# BC95_SIM.net
KiCad netlist of a schematic drawn in Altium Designer
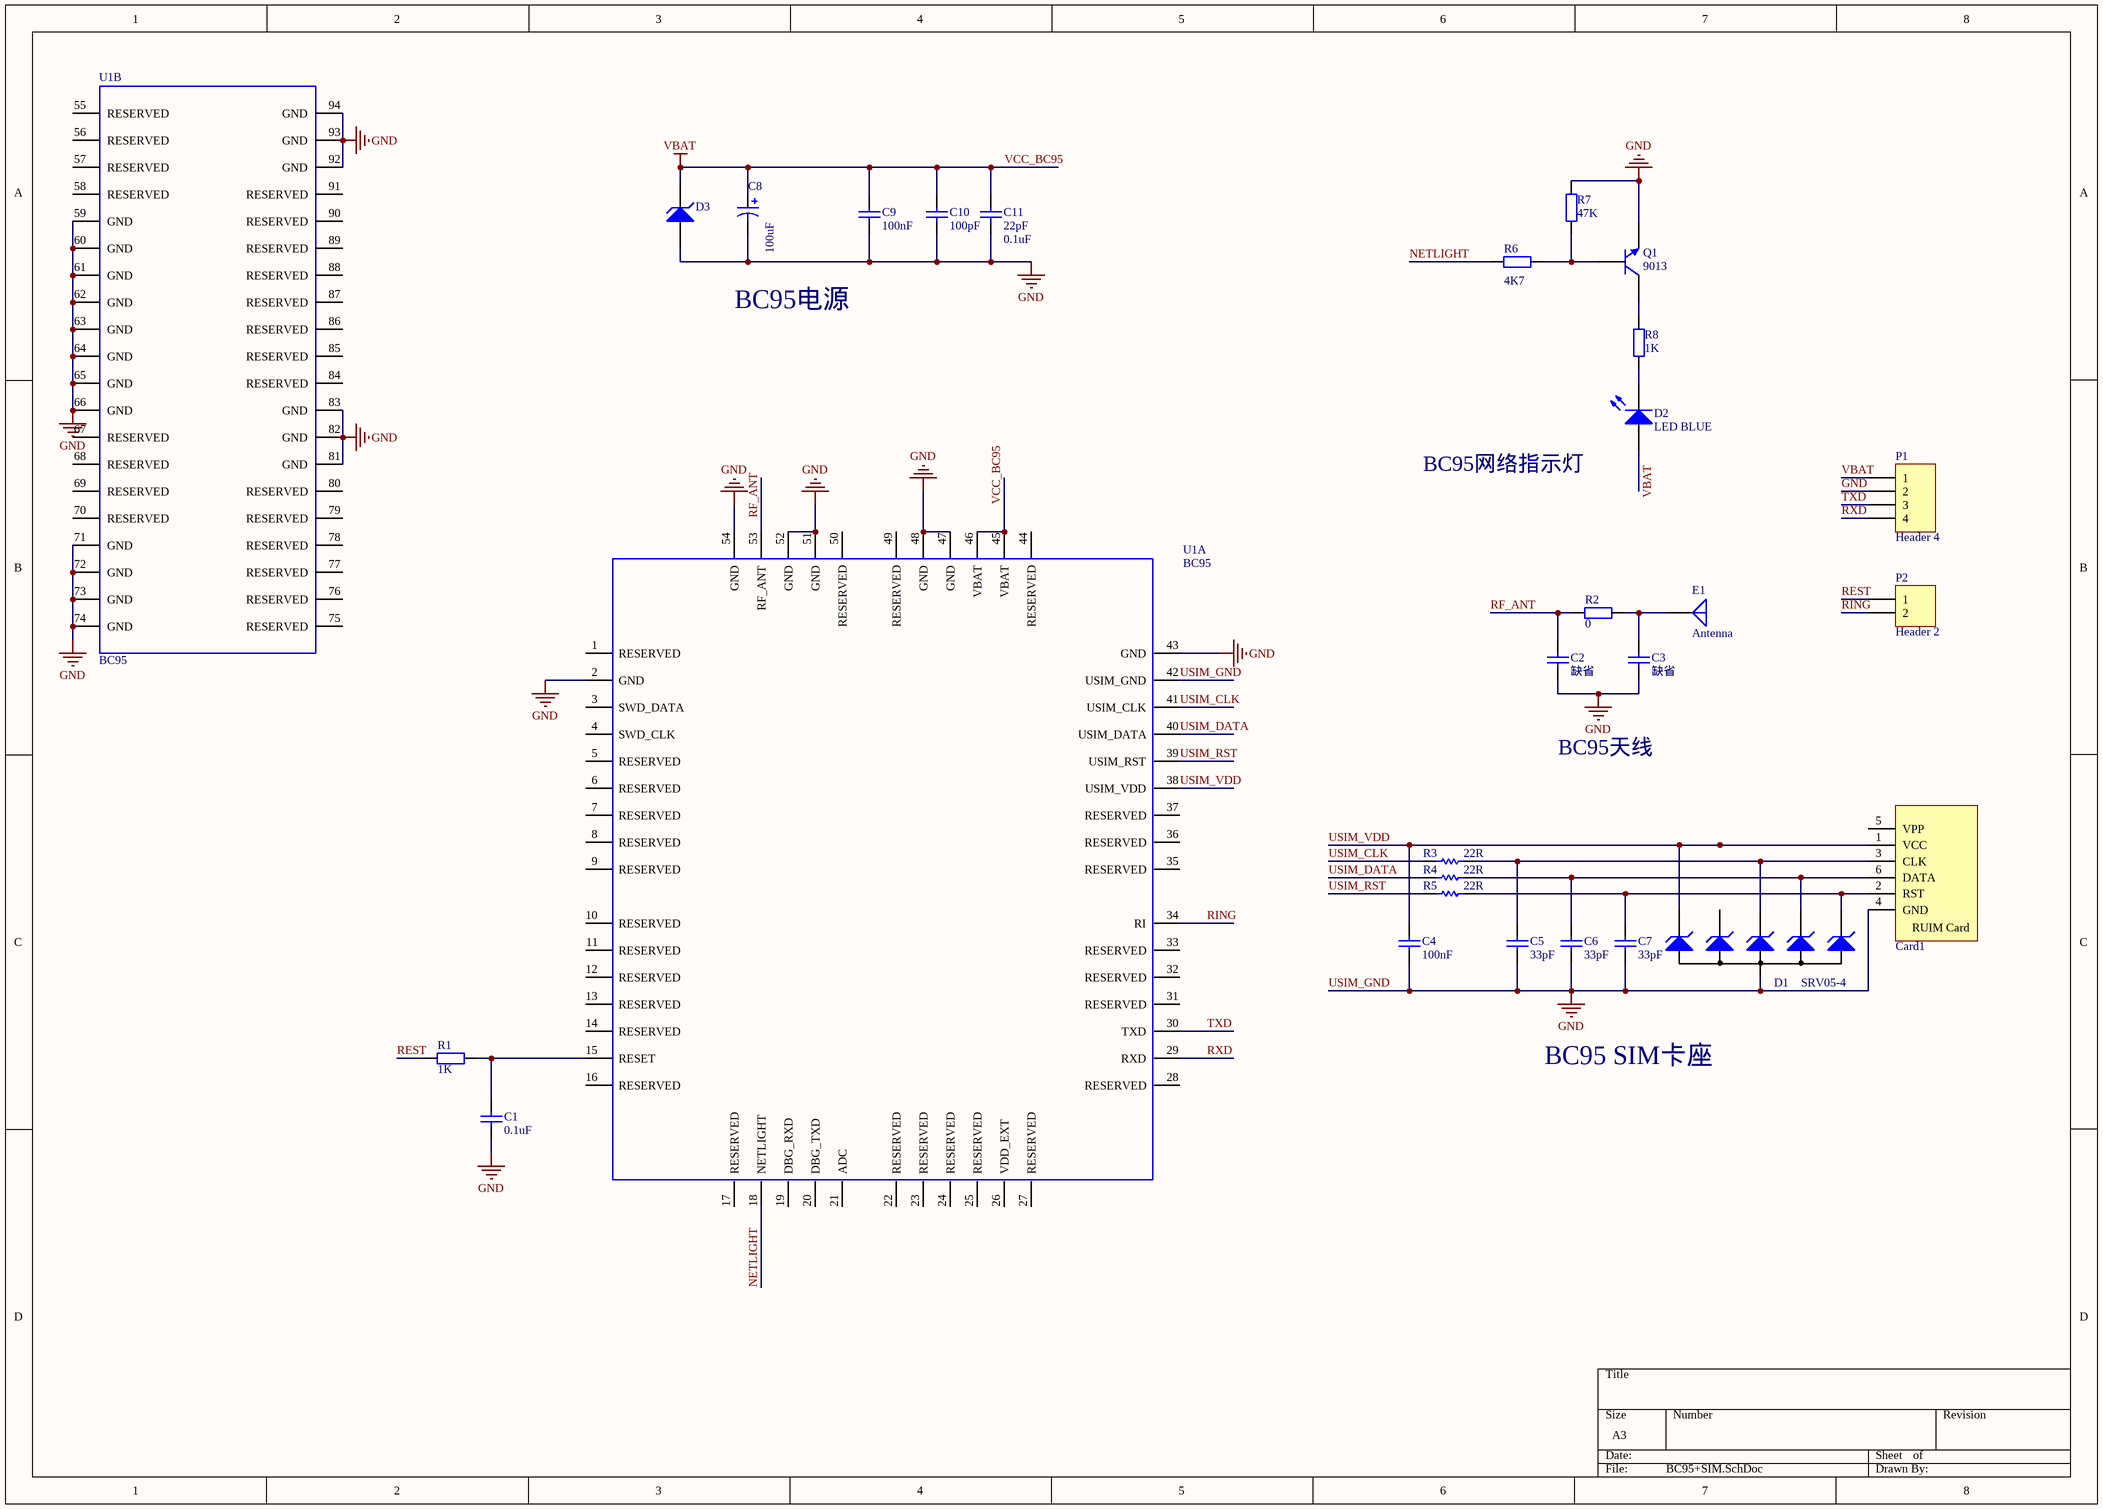
[diagram p0: BC95+SIM.SchDoc]

(export (version "E")
  (design (tool "Eeschema 10.0.6"))
  (components
    (comp (ref "C1")
      (value "0.1uF")
      (footprint "0603")
      (description "Capacitor")
      (fields (field (name "PUBLISHER") "Altium Limited"))
      (libsource (lib "Miscellaneous Devices") (part "Cap"))
    )
    (comp (ref "C2")
      (value "缺省")
      (footprint "0603")
      (description "Capacitor")
      (fields (field (name "PUBLISHER") "Altium Limited"))
      (libsource (lib "Miscellaneous Devices") (part "Cap"))
    )
    (comp (ref "C3")
      (value "缺省")
      (footprint "0603")
      (description "Capacitor")
      (fields (field (name "PUBLISHER") "Altium Limited"))
      (libsource (lib "Miscellaneous Devices") (part "Cap"))
    )
    (comp (ref "C4")
      (value "100nF")
      (footprint "0603")
      (description "Capacitor")
      (fields (field (name "PUBLISHER") "Altium Limited"))
      (libsource (lib "Miscellaneous Devices") (part "Cap"))
    )
    (comp (ref "C5")
      (value "33pF")
      (footprint "0603")
      (description "Capacitor")
      (fields (field (name "PUBLISHER") "Altium Limited"))
      (libsource (lib "Miscellaneous Devices") (part "Cap"))
    )
    (comp (ref "C6")
      (value "33pF")
      (footprint "0603")
      (description "Capacitor")
      (fields (field (name "PUBLISHER") "Altium Limited"))
      (libsource (lib "Miscellaneous Devices") (part "Cap"))
    )
    (comp (ref "C7")
      (value "33pF")
      (footprint "0603")
      (description "Capacitor")
      (fields (field (name "PUBLISHER") "Altium Limited"))
      (libsource (lib "Miscellaneous Devices") (part "Cap"))
    )
    (comp (ref "C8")
      (value "100uF")
      (footprint "1206")
      (description "插件 电解电容 13*21")
      (fields (field (name "PUBLISHER") "Altium Limited"))
      (libsource (lib "Miscellaneous Devices") (part "Cap Pol1"))
    )
    (comp (ref "C9")
      (value "100nF")
      (footprint "0603")
      (description "Capacitor")
      (fields (field (name "PUBLISHER") "Altium Limited"))
      (libsource (lib "Miscellaneous Devices") (part "Cap"))
    )
    (comp (ref "C10")
      (value "100pF")
      (footprint "0603")
      (description "Capacitor")
      (fields (field (name "PUBLISHER") "Altium Limited"))
      (libsource (lib "Miscellaneous Devices") (part "Cap"))
    )
    (comp (ref "C11")
      (value "22pF")
      (footprint "0603")
      (description "Capacitor")
      (fields (field (name "ALTIUM_VALUE") "0.1uF") (field (name "PUBLISHER") "Altium Limited"))
      (libsource (lib "Miscellaneous Devices") (part "Cap"))
    )
    (comp (ref "Card1") (value "Card") (footprint "SIM") (libsource (lib "ZDHH") (part "Card")))
    (comp (ref "D1")
      (value "SRV05-4")
      (footprint "SOT23-6")
      (description "SOT363")
      (fields (field (name "PUBLISHER") "Altium Limited"))
      (libsource (lib "SCHLIB") (part "SMF05C"))
    )
    (comp (ref "D2")
      (value "LED BLUE")
      (footprint "LED-3mm")
      (description "插件 发光二极管 5mm 红发红光")
      (fields (field (name "PUBLISHER") "Altium Limited"))
      (libsource (lib "Miscellaneous Devices") (part "LED0"))
    )
    (comp (ref "D3")
      (value "D Zener")
      (footprint "DO-214AB")
      (description "Zener Diode")
      (fields (field (name "PUBLISHER") "Altium Limited"))
      (libsource (lib "Miscellaneous Devices") (part "D Zener"))
    )
    (comp (ref "E1")
      (value "Antenna")
      (footprint "IPX")
      (description "Generic Antenna")
      (fields (field (name "PUBLISHER") "Altium Limited"))
      (libsource (lib "Miscellaneous Devices") (part "Antenna"))
    )
    (comp (ref "P1")
      (value "Header 4")
      (footprint "HDR1X4")
      (description "Header, 4-Pin")
      (fields (field (name "PUBLISHER") "Altium Limited"))
      (libsource (lib "Miscellaneous Connectors") (part "Header 4"))
    )
    (comp (ref "P2")
      (value "Header 2")
      (footprint "HDR1X2")
      (description "Header, 2-Pin")
      (fields (field (name "PUBLISHER") "Altium Limited"))
      (libsource (lib "Miscellaneous Connectors") (part "Header 2"))
    )
    (comp (ref "Q1")
      (value "9013")
      (footprint "SOT-23")
      (description "贴片三极管MMBT5551 SOT-23")
      (fields (field (name "PUBLISHER") "Altium Limited"))
      (libsource (lib "MyMiscellaneousDevices") (part "NPN"))
    )
    (comp (ref "R1")
      (value "1K")
      (footprint "0603")
      (description "Resistor")
      (fields (field (name "PUBLISHER") "Altium Limited"))
      (libsource (lib "Miscellaneous Devices") (part "Res2"))
    )
    (comp (ref "R2")
      (value "0")
      (footprint "0603")
      (description "Resistor")
      (fields (field (name "PUBLISHER") "Altium Limited"))
      (libsource (lib "Miscellaneous Devices") (part "Res2"))
    )
    (comp (ref "R3")
      (value "22R")
      (footprint "0603")
      (description "贴片电阻 0603")
      (libsource (lib "Any") (part "Resistor"))
    )
    (comp (ref "R4")
      (value "22R")
      (footprint "0603")
      (description "贴片电阻 0603")
      (libsource (lib "Any") (part "Resistor"))
    )
    (comp (ref "R5")
      (value "22R")
      (footprint "0603")
      (description "贴片电阻 0603")
      (libsource (lib "Any") (part "Resistor"))
    )
    (comp (ref "R6")
      (value "4K7")
      (footprint "0603")
      (description "Resistor")
      (fields (field (name "Comment") "Res2") (field (name "PUBLISHER") "Altium Limited"))
      (libsource (lib "Miscellaneous Devices") (part "Res2"))
    )
    (comp (ref "R7")
      (value "47K")
      (footprint "0603")
      (description "Resistor")
      (fields (field (name "Comment") "Res2") (field (name "PUBLISHER") "Altium Limited"))
      (libsource (lib "") (part "Res2_1"))
    )
    (comp (ref "R8")
      (value "1K")
      (footprint "0603")
      (description "Resistor")
      (fields (field (name "Comment") "Res2") (field (name "PUBLISHER") "Altium Limited"))
      (libsource (lib "") (part "Res2_2"))
    )
    (comp (ref "U1")
      (value "BC95")
      (footprint "BC95")
      (libsource (lib "BC95_SCH_Part_Protel_20160919") (part "BC95"))
    )
  )
  (nets
    (net (code "1") (name "/NETLIGHT") (class "Default")
      (node (ref "R6") (pin "1") (pinfunction "1_1") (pintype "passive"))
      (node (ref "U1") (pin "18") (pinfunction "NETLIGHT_18") (pintype "passive"))
    )
    (net (code "2") (name "/REST") (class "Default")
      (node (ref "P2") (pin "1") (pinfunction "1_1") (pintype "passive"))
      (node (ref "R1") (pin "1") (pinfunction "1_1") (pintype "passive"))
    )
    (net (code "3") (name "/RF_ANT") (class "Default")
      (node (ref "C2") (pin "2") (pinfunction "2_2") (pintype "passive"))
      (node (ref "R2") (pin "1") (pinfunction "1_1") (pintype "passive"))
      (node (ref "U1") (pin "53") (pinfunction "RF_ANT_53") (pintype "passive"))
    )
    (net (code "4") (name "/RING") (class "Default")
      (node (ref "P2") (pin "2") (pinfunction "2_2") (pintype "passive"))
      (node (ref "U1") (pin "34") (pinfunction "RI_34") (pintype "passive"))
    )
    (net (code "5") (name "/RXD") (class "Default")
      (node (ref "P1") (pin "4") (pinfunction "4_4") (pintype "passive"))
      (node (ref "U1") (pin "29") (pinfunction "RXD_29") (pintype "passive"))
    )
    (net (code "6") (name "/TXD") (class "Default")
      (node (ref "P1") (pin "3") (pinfunction "3_3") (pintype "passive"))
      (node (ref "U1") (pin "30") (pinfunction "TXD_30") (pintype "passive"))
    )
    (net (code "7") (name "/USIM_CLK") (class "Default")
      (node (ref "R3") (pin "2") (pinfunction "2_2") (pintype "passive"))
      (node (ref "U1") (pin "41") (pinfunction "USIM_CLK_41") (pintype "passive"))
    )
    (net (code "8") (name "/USIM_DATA") (class "Default")
      (node (ref "R4") (pin "2") (pinfunction "2_2") (pintype "passive"))
      (node (ref "U1") (pin "40") (pinfunction "USIM_DATA_40") (pintype "passive"))
    )
    (net (code "9") (name "/USIM_RST") (class "Default")
      (node (ref "R5") (pin "2") (pinfunction "2_2") (pintype "passive"))
      (node (ref "U1") (pin "39") (pinfunction "USIM_RST_39") (pintype "passive"))
    )
    (net (code "10") (name "/USIM_VDD") (class "Default")
      (node (ref "C4") (pin "2") (pinfunction "2_2") (pintype "passive"))
      (node (ref "Card1") (pin "1") (pinfunction "VCC_1") (pintype "power_in"))
      (node (ref "D1") (pin "6") (pintype "passive"))
      (node (ref "U1") (pin "38") (pinfunction "USIM_VDD_38") (pintype "passive"))
    )
    (net (code "11") (name "GND") (class "Default")
      (node (ref "C1") (pin "2") (pinfunction "2_2") (pintype "passive"))
      (node (ref "C10") (pin "1") (pinfunction "1_1") (pintype "passive"))
      (node (ref "C11") (pin "1") (pinfunction "1_1") (pintype "passive"))
      (node (ref "C2") (pin "1") (pinfunction "1_1") (pintype "passive"))
      (node (ref "C3") (pin "1") (pinfunction "1_1") (pintype "passive"))
      (node (ref "C4") (pin "1") (pinfunction "1_1") (pintype "passive"))
      (node (ref "C5") (pin "1") (pinfunction "1_1") (pintype "passive"))
      (node (ref "C6") (pin "1") (pinfunction "1_1") (pintype "passive"))
      (node (ref "C7") (pin "1") (pinfunction "1_1") (pintype "passive"))
      (node (ref "C8") (pin "2") (pinfunction "2_2") (pintype "passive"))
      (node (ref "C9") (pin "1") (pinfunction "1_1") (pintype "passive"))
      (node (ref "Card1") (pin "4") (pinfunction "GND_4") (pintype "passive"))
      (node (ref "D1") (pin "2") (pintype "passive"))
      (node (ref "D3") (pin "1") (pinfunction "A_1") (pintype "passive"))
      (node (ref "P1") (pin "2") (pinfunction "2_2") (pintype "passive"))
      (node (ref "Q1") (pin "2") (pinfunction "E_2") (pintype "passive"))
      (node (ref "R7") (pin "2") (pinfunction "2_2") (pintype "passive"))
      (node (ref "U1") (pin "2") (pinfunction "GND_2") (pintype "passive"))
      (node (ref "U1") (pin "42") (pinfunction "USIM_GND_42") (pintype "passive"))
      (node (ref "U1") (pin "43") (pinfunction "GND_43") (pintype "passive"))
      (node (ref "U1") (pin "47") (pinfunction "GND_47") (pintype "passive"))
      (node (ref "U1") (pin "48") (pinfunction "GND_48") (pintype "passive"))
      (node (ref "U1") (pin "51") (pinfunction "GND_51") (pintype "passive"))
      (node (ref "U1") (pin "52") (pinfunction "GND_52") (pintype "passive"))
      (node (ref "U1") (pin "54") (pinfunction "GND_54") (pintype "passive"))
      (node (ref "U1") (pin "59") (pinfunction "GND_59") (pintype "passive"))
      (node (ref "U1") (pin "60") (pinfunction "GND_60") (pintype "passive"))
      (node (ref "U1") (pin "61") (pinfunction "GND_61") (pintype "passive"))
      (node (ref "U1") (pin "62") (pinfunction "GND_62") (pintype "passive"))
      (node (ref "U1") (pin "63") (pinfunction "GND_63") (pintype "passive"))
      (node (ref "U1") (pin "64") (pinfunction "GND_64") (pintype "passive"))
      (node (ref "U1") (pin "65") (pinfunction "GND_65") (pintype "passive"))
      (node (ref "U1") (pin "66") (pinfunction "GND_66") (pintype "passive"))
      (node (ref "U1") (pin "71") (pinfunction "GND_71") (pintype "passive"))
      (node (ref "U1") (pin "72") (pinfunction "GND_72") (pintype "passive"))
      (node (ref "U1") (pin "73") (pinfunction "GND_73") (pintype "passive"))
      (node (ref "U1") (pin "74") (pinfunction "GND_74") (pintype "passive"))
      (node (ref "U1") (pin "81") (pinfunction "GND_81") (pintype "passive"))
      (node (ref "U1") (pin "82") (pinfunction "GND_82") (pintype "passive"))
      (node (ref "U1") (pin "83") (pinfunction "GND_83") (pintype "passive"))
      (node (ref "U1") (pin "92") (pinfunction "GND_92") (pintype "passive"))
      (node (ref "U1") (pin "93") (pinfunction "GND_93") (pintype "passive"))
      (node (ref "U1") (pin "94") (pinfunction "GND_94") (pintype "passive"))
    )
    (net (code "12") (name "Net-(Card1-CLK)") (class "Default")
      (node (ref "C5") (pin "2") (pinfunction "2_2") (pintype "passive"))
      (node (ref "Card1") (pin "3") (pinfunction "CLK_3") (pintype "power_in"))
      (node (ref "D1") (pin "4") (pintype "passive"))
      (node (ref "R3") (pin "1") (pinfunction "1_1") (pintype "passive"))
    )
    (net (code "13") (name "Net-(Card1-DATA)") (class "Default")
      (node (ref "C6") (pin "2") (pinfunction "2_2") (pintype "passive"))
      (node (ref "Card1") (pin "6") (pinfunction "DATA_6") (pintype "power_in"))
      (node (ref "D1") (pin "3") (pintype "passive"))
      (node (ref "R4") (pin "1") (pinfunction "1_1") (pintype "passive"))
    )
    (net (code "14") (name "Net-(Card1-RST)") (class "Default")
      (node (ref "C7") (pin "2") (pinfunction "2_2") (pintype "passive"))
      (node (ref "Card1") (pin "2") (pinfunction "RST_2") (pintype "power_in"))
      (node (ref "D1") (pin "1") (pintype "passive"))
      (node (ref "R5") (pin "1") (pinfunction "1_1") (pintype "passive"))
    )
    (net (code "15") (name "Net-(D2-K)") (class "Default")
      (node (ref "D2") (pin "2") (pinfunction "K_2") (pintype "passive"))
      (node (ref "R8") (pin "2") (pinfunction "2_2") (pintype "passive"))
    )
    (net (code "16") (name "Net-(E1-A)") (class "Default")
      (node (ref "C3") (pin "2") (pinfunction "2_2") (pintype "passive"))
      (node (ref "E1") (pin "1") (pinfunction "A_1") (pintype "passive"))
      (node (ref "R2") (pin "2") (pinfunction "2_2") (pintype "passive"))
    )
    (net (code "17") (name "Net-(Q1-B)") (class "Default")
      (node (ref "Q1") (pin "1") (pinfunction "B_1") (pintype "passive"))
      (node (ref "R6") (pin "2") (pinfunction "2_2") (pintype "passive"))
      (node (ref "R7") (pin "1") (pinfunction "1_1") (pintype "passive"))
    )
    (net (code "18") (name "Net-(Q1-C)") (class "Default")
      (node (ref "Q1") (pin "3") (pinfunction "C_3") (pintype "passive"))
      (node (ref "R8") (pin "1") (pinfunction "1_1") (pintype "passive"))
    )
    (net (code "19") (name "Net-(U1A-RESET)") (class "Default")
      (node (ref "C1") (pin "1") (pinfunction "1_1") (pintype "passive"))
      (node (ref "R1") (pin "2") (pinfunction "2_2") (pintype "passive"))
      (node (ref "U1") (pin "15") (pinfunction "RESET_15") (pintype "passive"))
    )
    (net (code "20") (name "VBAT") (class "Default")
      (node (ref "C10") (pin "2") (pinfunction "2_2") (pintype "passive"))
      (node (ref "C11") (pin "2") (pinfunction "2_2") (pintype "passive"))
      (node (ref "C8") (pin "1") (pinfunction "1_1") (pintype "passive"))
      (node (ref "C9") (pin "2") (pinfunction "2_2") (pintype "passive"))
      (node (ref "D2") (pin "1") (pinfunction "A_1") (pintype "passive"))
      (node (ref "D3") (pin "2") (pinfunction "K_2") (pintype "passive"))
      (node (ref "P1") (pin "1") (pinfunction "1_1") (pintype "passive"))
      (node (ref "U1") (pin "45") (pinfunction "VBAT_45") (pintype "passive"))
      (node (ref "U1") (pin "46") (pinfunction "VBAT_46") (pintype "passive"))
    )
    (net (code "21") (name "unconnected-(Card1-VPP-Pad5)") (class "Default")
      (node (ref "Card1") (pin "5") (pinfunction "VPP_5") (pintype "power_in"))
    )
    (net (code "22") (name "unconnected-(D1-Pad5)") (class "Default")
      (node (ref "D1") (pin "5") (pintype "passive"))
    )
    (net (code "23") (name "unconnected-(U1A-ADC-Pad21)") (class "Default")
      (node (ref "U1") (pin "21") (pinfunction "ADC_21") (pintype "passive"))
    )
    (net (code "24") (name "unconnected-(U1A-DBG_RXD-Pad19)") (class "Default")
      (node (ref "U1") (pin "19") (pinfunction "DBG_RXD_19") (pintype "passive"))
    )
    (net (code "25") (name "unconnected-(U1A-DBG_TXD-Pad20)") (class "Default")
      (node (ref "U1") (pin "20") (pinfunction "DBG_TXD_20") (pintype "passive"))
    )
    (net (code "26") (name "unconnected-(U1A-RESERVED-Pad1)") (class "Default")
      (node (ref "U1") (pin "1") (pinfunction "RESERVED_1") (pintype "passive"))
    )
    (net (code "27") (name "unconnected-(U1A-RESERVED-Pad5)") (class "Default")
      (node (ref "U1") (pin "5") (pinfunction "RESERVED_5") (pintype "passive"))
    )
    (net (code "28") (name "unconnected-(U1A-RESERVED-Pad6)") (class "Default")
      (node (ref "U1") (pin "6") (pinfunction "RESERVED_6") (pintype "passive"))
    )
    (net (code "29") (name "unconnected-(U1A-RESERVED-Pad7)") (class "Default")
      (node (ref "U1") (pin "7") (pinfunction "RESERVED_7") (pintype "passive"))
    )
    (net (code "30") (name "unconnected-(U1A-RESERVED-Pad8)") (class "Default")
      (node (ref "U1") (pin "8") (pinfunction "RESERVED_8") (pintype "passive"))
    )
    (net (code "31") (name "unconnected-(U1A-RESERVED-Pad9)") (class "Default")
      (node (ref "U1") (pin "9") (pinfunction "RESERVED_9") (pintype "passive"))
    )
    (net (code "32") (name "unconnected-(U1A-RESERVED-Pad10)") (class "Default")
      (node (ref "U1") (pin "10") (pinfunction "RESERVED_10") (pintype "passive"))
    )
    (net (code "33") (name "unconnected-(U1A-RESERVED-Pad11)") (class "Default")
      (node (ref "U1") (pin "11") (pinfunction "RESERVED_11") (pintype "passive"))
    )
    (net (code "34") (name "unconnected-(U1A-RESERVED-Pad12)") (class "Default")
      (node (ref "U1") (pin "12") (pinfunction "RESERVED_12") (pintype "passive"))
    )
    (net (code "35") (name "unconnected-(U1A-RESERVED-Pad13)") (class "Default")
      (node (ref "U1") (pin "13") (pinfunction "RESERVED_13") (pintype "passive"))
    )
    (net (code "36") (name "unconnected-(U1A-RESERVED-Pad14)") (class "Default")
      (node (ref "U1") (pin "14") (pinfunction "RESERVED_14") (pintype "passive"))
    )
    (net (code "37") (name "unconnected-(U1A-RESERVED-Pad16)") (class "Default")
      (node (ref "U1") (pin "16") (pinfunction "RESERVED_16") (pintype "passive"))
    )
    (net (code "38") (name "unconnected-(U1A-RESERVED-Pad17)") (class "Default")
      (node (ref "U1") (pin "17") (pinfunction "RESERVED_17") (pintype "passive"))
    )
    (net (code "39") (name "unconnected-(U1A-RESERVED-Pad22)") (class "Default")
      (node (ref "U1") (pin "22") (pinfunction "RESERVED_22") (pintype "passive"))
    )
    (net (code "40") (name "unconnected-(U1A-RESERVED-Pad23)") (class "Default")
      (node (ref "U1") (pin "23") (pinfunction "RESERVED_23") (pintype "passive"))
    )
    (net (code "41") (name "unconnected-(U1A-RESERVED-Pad24)") (class "Default")
      (node (ref "U1") (pin "24") (pinfunction "RESERVED_24") (pintype "passive"))
    )
    (net (code "42") (name "unconnected-(U1A-RESERVED-Pad25)") (class "Default")
      (node (ref "U1") (pin "25") (pinfunction "RESERVED_25") (pintype "passive"))
    )
    (net (code "43") (name "unconnected-(U1A-RESERVED-Pad27)") (class "Default")
      (node (ref "U1") (pin "27") (pinfunction "RESERVED_27") (pintype "passive"))
    )
    (net (code "44") (name "unconnected-(U1A-RESERVED-Pad28)") (class "Default")
      (node (ref "U1") (pin "28") (pinfunction "RESERVED_28") (pintype "passive"))
    )
    (net (code "45") (name "unconnected-(U1A-RESERVED-Pad31)") (class "Default")
      (node (ref "U1") (pin "31") (pinfunction "RESERVED_31") (pintype "passive"))
    )
    (net (code "46") (name "unconnected-(U1A-RESERVED-Pad32)") (class "Default")
      (node (ref "U1") (pin "32") (pinfunction "RESERVED_32") (pintype "passive"))
    )
    (net (code "47") (name "unconnected-(U1A-RESERVED-Pad33)") (class "Default")
      (node (ref "U1") (pin "33") (pinfunction "RESERVED_33") (pintype "passive"))
    )
    (net (code "48") (name "unconnected-(U1A-RESERVED-Pad35)") (class "Default")
      (node (ref "U1") (pin "35") (pinfunction "RESERVED_35") (pintype "passive"))
    )
    (net (code "49") (name "unconnected-(U1A-RESERVED-Pad36)") (class "Default")
      (node (ref "U1") (pin "36") (pinfunction "RESERVED_36") (pintype "passive"))
    )
    (net (code "50") (name "unconnected-(U1A-RESERVED-Pad37)") (class "Default")
      (node (ref "U1") (pin "37") (pinfunction "RESERVED_37") (pintype "passive"))
    )
    (net (code "51") (name "unconnected-(U1A-RESERVED-Pad44)") (class "Default")
      (node (ref "U1") (pin "44") (pinfunction "RESERVED_44") (pintype "passive"))
    )
    (net (code "52") (name "unconnected-(U1A-RESERVED-Pad49)") (class "Default")
      (node (ref "U1") (pin "49") (pinfunction "RESERVED_49") (pintype "passive"))
    )
    (net (code "53") (name "unconnected-(U1A-RESERVED-Pad50)") (class "Default")
      (node (ref "U1") (pin "50") (pinfunction "RESERVED_50") (pintype "passive"))
    )
    (net (code "54") (name "unconnected-(U1A-SWD_CLK-Pad4)") (class "Default")
      (node (ref "U1") (pin "4") (pinfunction "SWD_CLK_4") (pintype "passive"))
    )
    (net (code "55") (name "unconnected-(U1A-SWD_DATA-Pad3)") (class "Default")
      (node (ref "U1") (pin "3") (pinfunction "SWD_DATA_3") (pintype "passive"))
    )
    (net (code "56") (name "unconnected-(U1A-VDD_EXT-Pad26)") (class "Default")
      (node (ref "U1") (pin "26") (pinfunction "VDD_EXT_26") (pintype "passive"))
    )
    (net (code "57") (name "unconnected-(U1B-RESERVED-Pad55)") (class "Default")
      (node (ref "U1") (pin "55") (pinfunction "RESERVED_55") (pintype "passive"))
    )
    (net (code "58") (name "unconnected-(U1B-RESERVED-Pad56)") (class "Default")
      (node (ref "U1") (pin "56") (pinfunction "RESERVED_56") (pintype "passive"))
    )
    (net (code "59") (name "unconnected-(U1B-RESERVED-Pad57)") (class "Default")
      (node (ref "U1") (pin "57") (pinfunction "RESERVED_57") (pintype "passive"))
    )
    (net (code "60") (name "unconnected-(U1B-RESERVED-Pad58)") (class "Default")
      (node (ref "U1") (pin "58") (pinfunction "RESERVED_58") (pintype "passive"))
    )
    (net (code "61") (name "unconnected-(U1B-RESERVED-Pad67)") (class "Default")
      (node (ref "U1") (pin "67") (pinfunction "RESERVED_67") (pintype "passive"))
    )
    (net (code "62") (name "unconnected-(U1B-RESERVED-Pad68)") (class "Default")
      (node (ref "U1") (pin "68") (pinfunction "RESERVED_68") (pintype "passive"))
    )
    (net (code "63") (name "unconnected-(U1B-RESERVED-Pad69)") (class "Default")
      (node (ref "U1") (pin "69") (pinfunction "RESERVED_69") (pintype "passive"))
    )
    (net (code "64") (name "unconnected-(U1B-RESERVED-Pad70)") (class "Default")
      (node (ref "U1") (pin "70") (pinfunction "RESERVED_70") (pintype "passive"))
    )
    (net (code "65") (name "unconnected-(U1B-RESERVED-Pad75)") (class "Default")
      (node (ref "U1") (pin "75") (pinfunction "RESERVED_75") (pintype "passive"))
    )
    (net (code "66") (name "unconnected-(U1B-RESERVED-Pad76)") (class "Default")
      (node (ref "U1") (pin "76") (pinfunction "RESERVED_76") (pintype "passive"))
    )
    (net (code "67") (name "unconnected-(U1B-RESERVED-Pad77)") (class "Default")
      (node (ref "U1") (pin "77") (pinfunction "RESERVED_77") (pintype "passive"))
    )
    (net (code "68") (name "unconnected-(U1B-RESERVED-Pad78)") (class "Default")
      (node (ref "U1") (pin "78") (pinfunction "RESERVED_78") (pintype "passive"))
    )
    (net (code "69") (name "unconnected-(U1B-RESERVED-Pad79)") (class "Default")
      (node (ref "U1") (pin "79") (pinfunction "RESERVED_79") (pintype "passive"))
    )
    (net (code "70") (name "unconnected-(U1B-RESERVED-Pad80)") (class "Default")
      (node (ref "U1") (pin "80") (pinfunction "RESERVED_80") (pintype "passive"))
    )
    (net (code "71") (name "unconnected-(U1B-RESERVED-Pad84)") (class "Default")
      (node (ref "U1") (pin "84") (pinfunction "RESERVED_84") (pintype "passive"))
    )
    (net (code "72") (name "unconnected-(U1B-RESERVED-Pad85)") (class "Default")
      (node (ref "U1") (pin "85") (pinfunction "RESERVED_85") (pintype "passive"))
    )
    (net (code "73") (name "unconnected-(U1B-RESERVED-Pad86)") (class "Default")
      (node (ref "U1") (pin "86") (pinfunction "RESERVED_86") (pintype "passive"))
    )
    (net (code "74") (name "unconnected-(U1B-RESERVED-Pad87)") (class "Default")
      (node (ref "U1") (pin "87") (pinfunction "RESERVED_87") (pintype "passive"))
    )
    (net (code "75") (name "unconnected-(U1B-RESERVED-Pad88)") (class "Default")
      (node (ref "U1") (pin "88") (pinfunction "RESERVED_88") (pintype "passive"))
    )
    (net (code "76") (name "unconnected-(U1B-RESERVED-Pad89)") (class "Default")
      (node (ref "U1") (pin "89") (pinfunction "RESERVED_89") (pintype "passive"))
    )
    (net (code "77") (name "unconnected-(U1B-RESERVED-Pad90)") (class "Default")
      (node (ref "U1") (pin "90") (pinfunction "RESERVED_90") (pintype "passive"))
    )
    (net (code "78") (name "unconnected-(U1B-RESERVED-Pad91)") (class "Default")
      (node (ref "U1") (pin "91") (pinfunction "RESERVED_91") (pintype "passive"))
    )
  )
)
